# ROBOCON_25_SCHEMATIC_json.net
KiCad netlist of a schematic drawn in EasyEDA
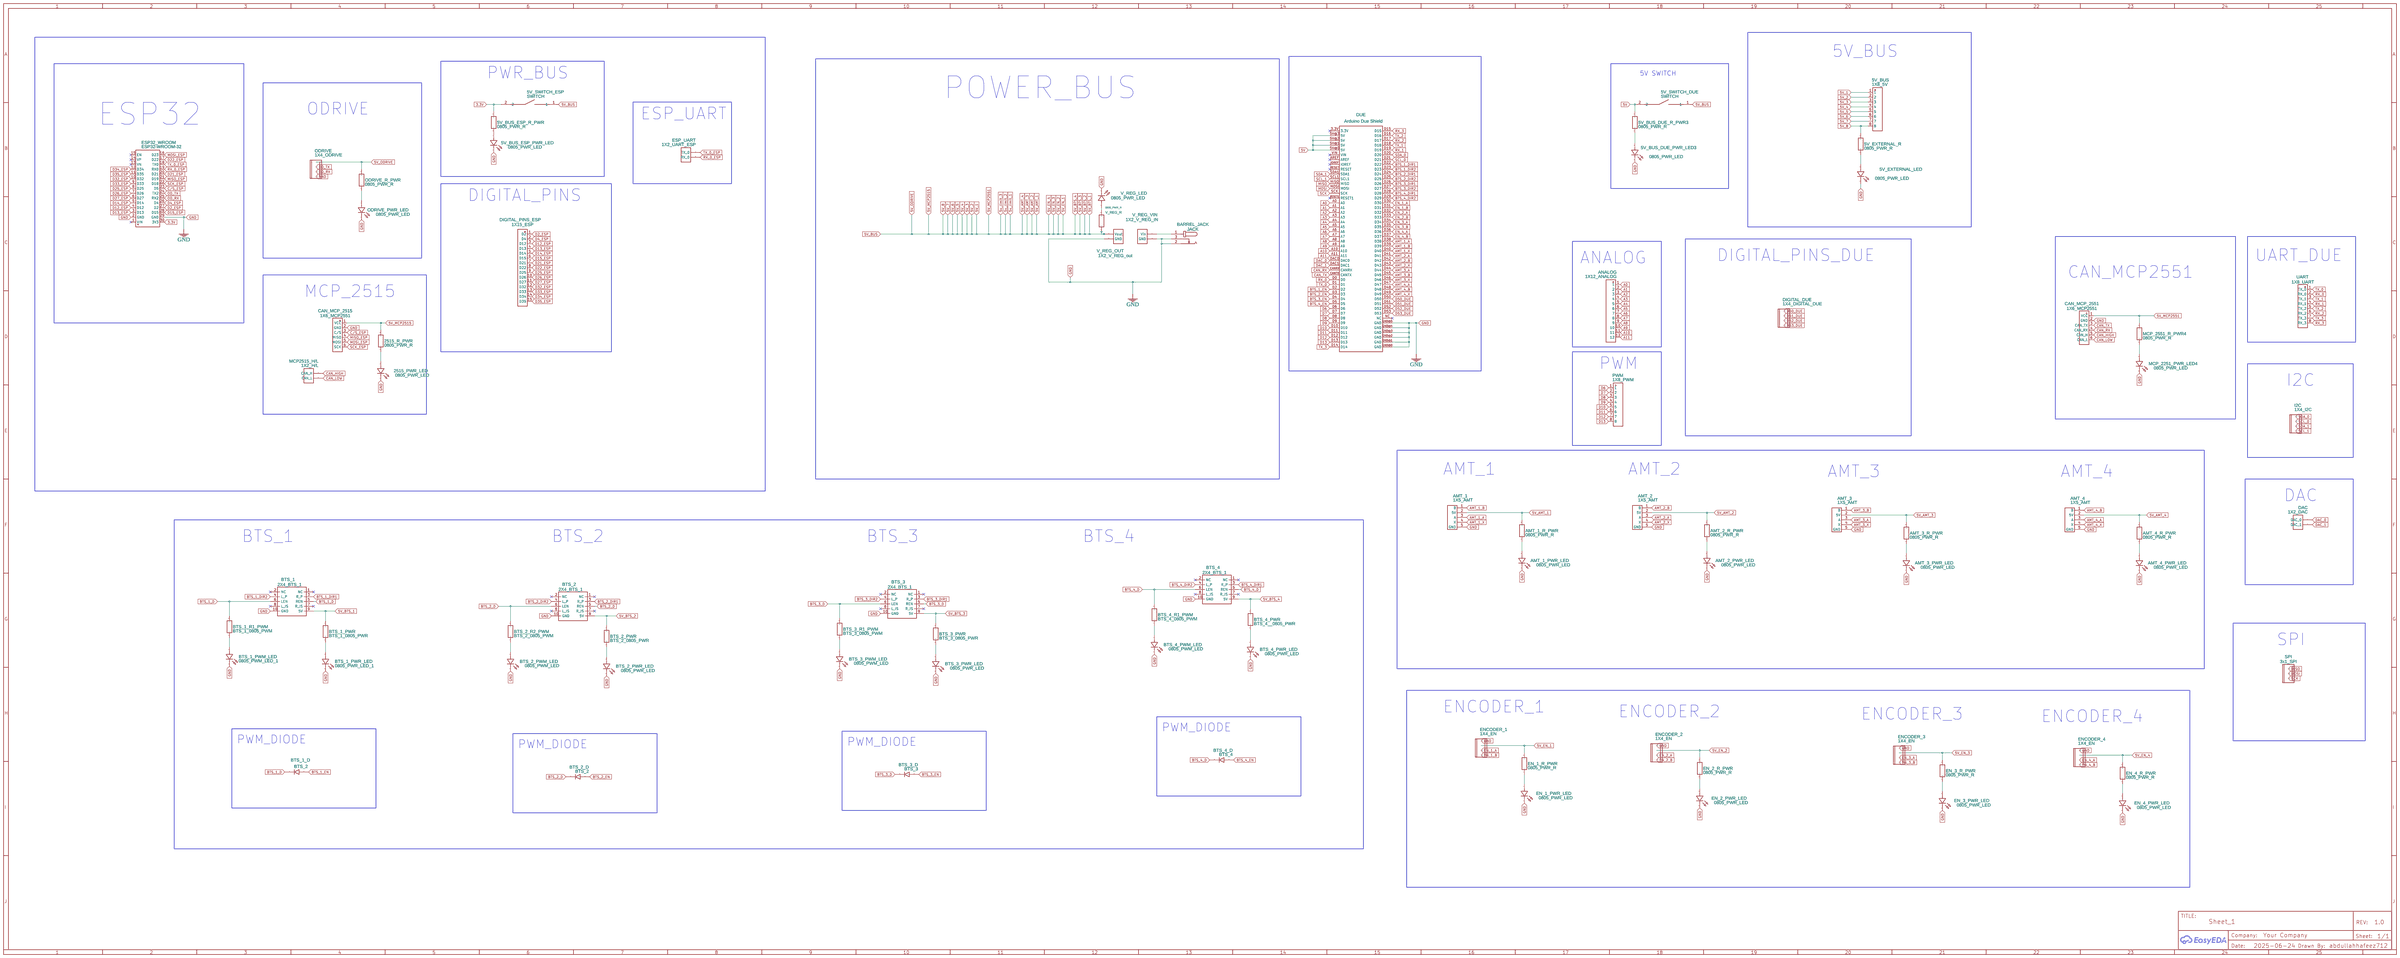
[diagram p0: schematic sheet]

(export (version "E")
  (design (tool "Eeschema 10.0.6"))
  (components
    (comp (ref "5V_BUS")
      (value "1X8_5V")
      (fields
        (field (name "Manufacturer Part") "HC-PZ200-8.7L-1x8PZ")
        (field (name "Manufacturer") "HC(虹成电子)")
      )
      (libsource (lib "") (part "HC-PZ200-8.7L-1X8PZ_2"))
    )
    (comp (ref "5V_BUS_DUE_PWR_LED3")
      (value "0805_PWR_LED")
      (fields (field (name "Manufacturer Part") "YLED0805YG") (field (name "Manufacturer") "YONGYUTAI(永裕泰)"))
      (libsource (lib "") (part "YLED0805YG_20"))
    )
    (comp (ref "5V_BUS_DUE_R_PWR3") (value "0805_PWR_R") (libsource (lib "") (part "RESISTOR-SMD-1206_6")))
    (comp (ref "5V_BUS_ESP_PWR_LED")
      (value "0805_PWR_LED")
      (fields (field (name "Manufacturer Part") "YLED0805YG") (field (name "Manufacturer") "YONGYUTAI(永裕泰)"))
      (libsource (lib "") (part "YLED0805YG_2"))
    )
    (comp (ref "5V_BUS_ESP_R_PWR") (value "0805_PWR_R") (libsource (lib "") (part "RESISTOR-SMD-1206")))
    (comp (ref "5V_EXTERNAL_LED")
      (value "0805_PWR_LED")
      (fields (field (name "Manufacturer Part") "YLED0805YG") (field (name "Manufacturer") "YONGYUTAI(永裕泰)"))
      (libsource (lib "") (part "YLED0805YG_4"))
    )
    (comp (ref "5V_EXTERNAL_R") (value "0805_PWR_R") (libsource (lib "") (part "RESISTOR-SMD-1206_2")))
    (comp (ref "5V_SWITCH_DUE") (value "SWITCH") (libsource (lib "") (part "Tactile switch SMD 2 Pin")))
    (comp (ref "5V_SWITCH_ESP") (value "SWITCH") (libsource (lib "") (part "Tactile switch SMD 2 Pin_1")))
    (comp (ref "2515_PWR_LED")
      (value "0805_PWR_LED")
      (fields (field (name "Manufacturer Part") "YLED0805YG") (field (name "Manufacturer") "YONGYUTAI(永裕泰)"))
      (libsource (lib "") (part "YLED0805YG_19"))
    )
    (comp (ref "2515_R_PWR") (value "0805_PWR_R") (libsource (lib "") (part "RESISTOR-SMD-1206_10")))
    (comp (ref "AMT_1")
      (value "1X5_AMT")
      (fields (field (name "Manufacturer Part") "XHB-5A") (field (name "Manufacturer") "BOOMELE(博穆精密)"))
      (libsource (lib "") (part "XHB-5A"))
    )
    (comp (ref "AMT_1_PWR_LED")
      (value "0805_PWR_LED")
      (fields (field (name "Manufacturer Part") "YLED0805YG") (field (name "Manufacturer") "YONGYUTAI(永裕泰)"))
      (libsource (lib "") (part "YLED0805YG_15"))
    )
    (comp (ref "AMT_1_R_PWR") (value "0805_PWR_R") (libsource (lib "") (part "RESISTOR-SMD-1206_12")))
    (comp (ref "AMT_2")
      (value "1X5_AMT")
      (fields (field (name "Manufacturer Part") "XHB-5A") (field (name "Manufacturer") "BOOMELE(博穆精密)"))
      (libsource (lib "") (part "XHB-5A"))
    )
    (comp (ref "AMT_2_PWR_LED")
      (value "0805_PWR_LED")
      (fields (field (name "Manufacturer Part") "YLED0805YG") (field (name "Manufacturer") "YONGYUTAI(永裕泰)"))
      (libsource (lib "") (part "YLED0805YG_12"))
    )
    (comp (ref "AMT_2_R_PWR") (value "0805_PWR_R") (libsource (lib "") (part "RESISTOR-SMD-1206_5")))
    (comp (ref "AMT_3")
      (value "1X5_AMT")
      (fields (field (name "Manufacturer Part") "XHB-5A") (field (name "Manufacturer") "BOOMELE(博穆精密)"))
      (libsource (lib "") (part "XHB-5A"))
    )
    (comp (ref "AMT_3_PWR_LED")
      (value "0805_PWR_LED")
      (fields (field (name "Manufacturer Part") "YLED0805YG") (field (name "Manufacturer") "YONGYUTAI(永裕泰)"))
      (libsource (lib "") (part "YLED0805YG_6"))
    )
    (comp (ref "AMT_3_R_PWR") (value "0805_PWR_R") (libsource (lib "") (part "RESISTOR-SMD-1206_17")))
    (comp (ref "AMT_4")
      (value "1X5_AMT")
      (fields (field (name "Manufacturer Part") "XHB-5A") (field (name "Manufacturer") "BOOMELE(博穆精密)"))
      (libsource (lib "") (part "XHB-5A"))
    )
    (comp (ref "AMT_4_PWR_LED")
      (value "0805_PWR_LED")
      (fields (field (name "Manufacturer Part") "YLED0805YG") (field (name "Manufacturer") "YONGYUTAI(永裕泰)"))
      (libsource (lib "") (part "YLED0805YG_1"))
    )
    (comp (ref "AMT_4_R_PWR") (value "0805_PWR_R") (libsource (lib "") (part "RESISTOR-SMD-1206_7")))
    (comp (ref "ANALOG")
      (value "1X12_ANALOG")
      (fields
        (field (name "Manufacturer Part") "KH-2FH-1X12P-H4.3")
        (field (name "Manufacturer") "kinghelm(金航标)")
      )
      (libsource (lib "") (part "KH-2FH-1X12P-H4.3"))
    )
    (comp (ref "BARREL_JACK")
      (value "JACK")
      (fields (field (name "Manufacturer Part") "PJ-002AH") (field (name "Manufacturer") "CUI"))
      (libsource (lib "") (part "PJ-002AH"))
    )
    (comp (ref "BTS_1") (value "2X4_BTS_1") (libsource (lib "") (part "IDC-10_(2X5)_2,54_BOX")))
    (comp (ref "BTS_1_D")
      (value "BTS_2")
      (fields (field (name "Manufacturer Part") "IRFD9120PbF"))
      (libsource (lib "") (part "IN4007_2"))
    )
    (comp (ref "BTS_1_PWM_LED")
      (value "0805_PWM_LED_1")
      (fields (field (name "Manufacturer Part") "YLED0805YG") (field (name "Manufacturer") "YONGYUTAI(永裕泰)"))
      (libsource (lib "") (part "YLED0805YG_18"))
    )
    (comp (ref "BTS_1_PWR") (value "BTS_1_0805_PWR") (libsource (lib "") (part "RESISTOR-SMD-1206_14")))
    (comp (ref "BTS_1_PWR_LED")
      (value "0805_PWR_LED_1")
      (fields (field (name "Manufacturer Part") "YLED0805YG") (field (name "Manufacturer") "YONGYUTAI(永裕泰)"))
      (libsource (lib "") (part "YLED0805YG_11"))
    )
    (comp (ref "BTS_1_R1_PWM") (value "BTS_1_0805_PWM") (libsource (lib "") (part "RESISTOR-SMD-1206_1")))
    (comp (ref "BTS_2") (value "2X4_BTS_1") (libsource (lib "") (part "IDC-10_(2X5)_2,54_BOX")))
    (comp (ref "BTS_2_D")
      (value "BTS_2")
      (fields (field (name "Manufacturer Part") "IRFD9120PbF"))
      (libsource (lib "") (part "IN4007_1"))
    )
    (comp (ref "BTS_2_PWM_LED")
      (value "0805_PWM_LED")
      (fields (field (name "Manufacturer Part") "YLED0805YG") (field (name "Manufacturer") "YONGYUTAI(永裕泰)"))
      (libsource (lib "") (part "YLED0805YG_5"))
    )
    (comp (ref "BTS_2_PWR") (value "BTS_2_0805_PWR") (libsource (lib "") (part "RESISTOR-SMD-1206_9")))
    (comp (ref "BTS_2_PWR_LED")
      (value "0805_PWR_LED")
      (fields (field (name "Manufacturer Part") "YLED0805YG") (field (name "Manufacturer") "YONGYUTAI(永裕泰)"))
      (libsource (lib "") (part "YLED0805YG_8"))
    )
    (comp (ref "BTS_2_R2_PWM") (value "BTS_2_0805_PWM") (libsource (lib "") (part "RESISTOR-SMD-1206_16")))
    (comp (ref "BTS_3") (value "2X4_BTS_1") (libsource (lib "") (part "IDC-10_(2X5)_2,54_BOX")))
    (comp (ref "BTS_3_D")
      (value "BTS_3")
      (fields (field (name "Manufacturer Part") "IRFD9120PbF"))
      (libsource (lib "") (part "IN4007"))
    )
    (comp (ref "BTS_3_PWM_LED")
      (value "0805_PWM_LED")
      (fields (field (name "Manufacturer Part") "YLED0805YG") (field (name "Manufacturer") "YONGYUTAI(永裕泰)"))
      (libsource (lib "") (part "YLED0805YG_10"))
    )
    (comp (ref "BTS_3_PWR") (value "BTS_3_0805_PWR") (libsource (lib "") (part "RESISTOR-SMD-1206_20")))
    (comp (ref "BTS_3_PWR_LED")
      (value "0805_PWR_LED")
      (fields (field (name "Manufacturer Part") "YLED0805YG") (field (name "Manufacturer") "YONGYUTAI(永裕泰)"))
      (libsource (lib "") (part "YLED0805YG_17"))
    )
    (comp (ref "BTS_3_R1_PWM") (value "BTS_3_0805_PWM") (libsource (lib "") (part "RESISTOR-SMD-1206_18")))
    (comp (ref "BTS_4") (value "2X4_BTS_1") (libsource (lib "") (part "IDC-10_(2X5)_2,54_BOX")))
    (comp (ref "BTS_4_D")
      (value "BTS_4")
      (fields (field (name "Manufacturer Part") "IRFD9120PbF"))
      (libsource (lib "") (part "IN4007_3"))
    )
    (comp (ref "BTS_4_PWM_LED")
      (value "0805_PWM_LED")
      (fields (field (name "Manufacturer Part") "YLED0805YG") (field (name "Manufacturer") "YONGYUTAI(永裕泰)"))
      (libsource (lib "") (part "YLED0805YG_9"))
    )
    (comp (ref "BTS_4_PWR") (value "BTS_4__0805_PWR") (libsource (lib "") (part "RESISTOR-SMD-1206_3")))
    (comp (ref "BTS_4_PWR_LED")
      (value "0805_PWR_LED")
      (fields (field (name "Manufacturer Part") "YLED0805YG") (field (name "Manufacturer") "YONGYUTAI(永裕泰)"))
      (libsource (lib "") (part "YLED0805YG_3"))
    )
    (comp (ref "BTS_4_R1_PWM") (value "BTS_4_0805_PWM") (libsource (lib "") (part "RESISTOR-SMD-1206_4")))
    (comp (ref "CAN_MCP_2515")
      (value "1X6_MCP2551")
      (fields (field (name "Manufacturer Part") "DS1021-1x6SF11-B") (field (name "Manufacturer") "CONNFLY"))
      (libsource (lib "") (part "DS1021-1X6SF11-B_1"))
    )
    (comp (ref "CAN_MCP_2551")
      (value "1X6_MCP2551")
      (fields (field (name "Manufacturer Part") "DS1021-1x6SF11-B") (field (name "Manufacturer") "CONNFLY"))
      (libsource (lib "") (part "DS1021-1X6SF11-B"))
    )
    (comp (ref "DAC")
      (value "1X2_DAC")
      (fields (field (name "Manufacturer Part") "RELIMATE CON 3 PIN"))
      (libsource (lib "") (part "2 pin RELIMATE copy_4"))
    )
    (comp (ref "DIGITAL_DUE")
      (value "1X4_DIGITAL_DUE")
      (libsource (lib "") (part "4PIN_RELIMATE_CONNECTOR_3"))
    )
    (comp (ref "DIGITAL_PINS_ESP")
      (value "1X15_ESP")
      (fields
        (field (name "Manufacturer Part") "HC-PM200-4.3H-1x15PZ")
        (field (name "Manufacturer") "HC(虹成电子)")
      )
      (libsource (lib "") (part "HC-PM200-4.3H-1X15PZ"))
    )
    (comp (ref "DUE")
      (value "Arduino Due Shield")
      (fields (field (name "Manufacturer Part") "ARDUINO DUE"))
      (libsource (lib "") (part "Arduino Due Shield"))
    )
    (comp (ref "ENCODER_1") (value "1X4_EN") (libsource (lib "") (part "4PIN_RELIMATE_CONNECTOR")))
    (comp (ref "ENCODER_2") (value "1X4_EN") (libsource (lib "") (part "4PIN_RELIMATE_CONNECTOR")))
    (comp (ref "ENCODER_3") (value "1X4_EN") (libsource (lib "") (part "4PIN_RELIMATE_CONNECTOR")))
    (comp (ref "ENCODER_4") (value "1X4_EN") (libsource (lib "") (part "4PIN_RELIMATE_CONNECTOR")))
    (comp (ref "EN_1_PWR_LED")
      (value "0805_PWR_LED")
      (fields (field (name "Manufacturer Part") "YLED0805YG") (field (name "Manufacturer") "YONGYUTAI(永裕泰)"))
      (libsource (lib "") (part "YLED0805YG_7"))
    )
    (comp (ref "EN_1_R_PWR") (value "0805_PWR_R") (libsource (lib "") (part "RESISTOR-SMD-1206_15")))
    (comp (ref "EN_2_PWR_LED")
      (value "0805_PWR_LED")
      (fields (field (name "Manufacturer Part") "YLED0805YG") (field (name "Manufacturer") "YONGYUTAI(永裕泰)"))
      (libsource (lib "") (part "YLED0805YG_14"))
    )
    (comp (ref "EN_2_R_PWR") (value "0805_PWR_R") (libsource (lib "") (part "RESISTOR-SMD-1206_19")))
    (comp (ref "EN_3_PWR_LED")
      (value "0805_PWR_LED")
      (fields (field (name "Manufacturer Part") "YLED0805YG") (field (name "Manufacturer") "YONGYUTAI(永裕泰)"))
      (libsource (lib "") (part "YLED0805YG_21"))
    )
    (comp (ref "EN_3_R_PWR") (value "0805_PWR_R") (libsource (lib "") (part "RESISTOR-SMD-1206_13")))
    (comp (ref "EN_4_PWR_LED")
      (value "0805_PWR_LED")
      (fields (field (name "Manufacturer Part") "YLED0805YG") (field (name "Manufacturer") "YONGYUTAI(永裕泰)"))
      (libsource (lib "") (part "YLED0805YG"))
    )
    (comp (ref "EN_4_R_PWR") (value "0805_PWR_R") (libsource (lib "") (part "RESISTOR-SMD-1206_22")))
    (comp (ref "ESP32_WROOM") (value "ESP32-WROOM-32") (libsource (lib "") (part "ESP32-WROOM-32-30Pin")))
    (comp (ref "ESP_UART")
      (value "1X2_UART_ESP")
      (fields (field (name "Manufacturer Part") "RELIMATE CON 3 PIN"))
      (libsource (lib "") (part "2 pin RELIMATE copy_3"))
    )
    (comp (ref "I2C") (value "1X4_I2C") (libsource (lib "") (part "4PIN_RELIMATE_CONNECTOR_1")))
    (comp (ref "MCP2515_H/L")
      (value "1X2_H/L")
      (fields (field (name "Manufacturer Part") "RELIMATE CON 3 PIN"))
      (libsource (lib "") (part "2 pin RELIMATE copy_1"))
    )
    (comp (ref "MCP_2251_PWR_LED4")
      (value "0805_PWR_LED")
      (fields (field (name "Manufacturer Part") "YLED0805YG") (field (name "Manufacturer") "YONGYUTAI(永裕泰)"))
      (libsource (lib "") (part "YLED0805YG_16"))
    )
    (comp (ref "MCP_2551_R_PWR4") (value "0805_PWR_R") (libsource (lib "") (part "RESISTOR-SMD-1206_8")))
    (comp (ref "ODRIVE") (value "1X4_ODRIVE") (libsource (lib "") (part "4PIN_RELIMATE_CONNECTOR_2")))
    (comp (ref "ODRIVE_PWR_LED")
      (value "0805_PWR_LED")
      (fields (field (name "Manufacturer Part") "YLED0805YG") (field (name "Manufacturer") "YONGYUTAI(永裕泰)"))
      (libsource (lib "") (part "YLED0805YG_22"))
    )
    (comp (ref "ODRIVE_R_PWR") (value "0805_PWR_R") (libsource (lib "") (part "RESISTOR-SMD-1206_11")))
    (comp (ref "PWM")
      (value "1X8_PWM")
      (fields
        (field (name "Manufacturer Part") "HC-PZ200-8.7L-1x8PZ")
        (field (name "Manufacturer") "HC(虹成电子)")
      )
      (libsource (lib "") (part "HC-PZ200-8.7L-1X8PZ"))
    )
    (comp (ref "SPI") (value "3x1_SPI") (libsource (lib "") (part "3PIN_RELIMATE_CONNECTOR")))
    (comp (ref "UART")
      (value "1X8_UART")
      (fields
        (field (name "Manufacturer Part") "HC-PZ200-8.7L-1x8PZ")
        (field (name "Manufacturer") "HC(虹成电子)")
      )
      (libsource (lib "") (part "HC-PZ200-8.7L-1X8PZ_1"))
    )
    (comp (ref "V_REG_LED")
      (value "0805_PWR_LED")
      (fields (field (name "Manufacturer Part") "YLED0805YG") (field (name "Manufacturer") "YONGYUTAI(永裕泰)"))
      (libsource (lib "") (part "YLED0805YG_13"))
    )
    (comp (ref "V_REG_OUT")
      (value "1X2_V_REG_out")
      (fields (field (name "Manufacturer Part") "RELIMATE CON 3 PIN"))
      (libsource (lib "") (part "2 pin RELIMATE copy"))
    )
    (comp (ref "V_REG_R") (value "0805_PWR_R") (libsource (lib "") (part "RESISTOR-SMD-1206_21")))
    (comp (ref "V_REG_VIN")
      (value "1X2_V_REG_IN")
      (fields (field (name "Manufacturer Part") "RELIMATE CON 3 PIN"))
      (libsource (lib "") (part "2 pin RELIMATE copy_2"))
    )
  )
  (nets
    (net (code "1") (name "3.3V") (class "Default")
      (node (ref "5V_BUS_ESP_R_PWR") (pin "2") (pinfunction "2_2") (pintype "unspecified"))
      (node (ref "5V_SWITCH_ESP") (pin "2") (pinfunction "2_2") (pintype "unspecified"))
      (node (ref "ESP32_WROOM") (pin "30") (pinfunction "3V3_30") (pintype "unspecified"))
    )
    (net (code "2") (name "5V") (class "Default")
      (node (ref "5V_BUS_DUE_R_PWR3") (pin "2") (pinfunction "2_2") (pintype "unspecified"))
      (node (ref "5V_SWITCH_DUE") (pin "2") (pinfunction "2_2") (pintype "unspecified"))
      (node (ref "DUE") (pin "5V@0") (pinfunction "5V_5V@0") (pintype "unspecified"))
      (node (ref "DUE") (pin "5V@1") (pinfunction "5V_5V@1") (pintype "unspecified"))
      (node (ref "DUE") (pin "5V@2") (pinfunction "5V_5V@2") (pintype "unspecified"))
      (node (ref "DUE") (pin "5V@3") (pinfunction "5V_5V@3") (pintype "unspecified"))
    )
    (net (code "3") (name "5V_1") (class "Default")
      (node (ref "2515_R_PWR") (pin "2") (pinfunction "2_2") (pintype "unspecified"))
      (node (ref "5V_BUS") (pin "1") (pinfunction "1_1") (pintype "unspecified"))
      (node (ref "5V_BUS") (pin "2") (pinfunction "2_2") (pintype "unspecified"))
      (node (ref "5V_BUS") (pin "3") (pinfunction "3_3") (pintype "unspecified"))
      (node (ref "5V_BUS") (pin "4") (pinfunction "4_4") (pintype "unspecified"))
      (node (ref "5V_BUS") (pin "5") (pinfunction "5_5") (pintype "unspecified"))
      (node (ref "5V_BUS") (pin "6") (pinfunction "6_6") (pintype "unspecified"))
      (node (ref "5V_BUS") (pin "7") (pinfunction "7_7") (pintype "unspecified"))
      (node (ref "5V_BUS") (pin "8") (pinfunction "8_8") (pintype "unspecified"))
      (node (ref "5V_EXTERNAL_R") (pin "2") (pinfunction "2_2") (pintype "unspecified"))
      (node (ref "5V_SWITCH_DUE") (pin "1") (pinfunction "1_1") (pintype "unspecified"))
      (node (ref "5V_SWITCH_ESP") (pin "1") (pinfunction "1_1") (pintype "unspecified"))
      (node (ref "AMT_1") (pin "2") (pinfunction "5V_2") (pintype "unspecified"))
      (node (ref "AMT_1_R_PWR") (pin "2") (pinfunction "2_2") (pintype "unspecified"))
      (node (ref "AMT_2") (pin "2") (pinfunction "5V_2") (pintype "unspecified"))
      (node (ref "AMT_2_R_PWR") (pin "2") (pinfunction "2_2") (pintype "unspecified"))
      (node (ref "AMT_3") (pin "2") (pinfunction "5V_2") (pintype "unspecified"))
      (node (ref "AMT_3_R_PWR") (pin "2") (pinfunction "2_2") (pintype "unspecified"))
      (node (ref "AMT_4") (pin "2") (pinfunction "5V_2") (pintype "unspecified"))
      (node (ref "AMT_4_R_PWR") (pin "2") (pinfunction "2_2") (pintype "unspecified"))
      (node (ref "BTS_1") (pin "9") (pinfunction "5V_9") (pintype "unspecified"))
      (node (ref "BTS_1_PWR") (pin "2") (pinfunction "2_2") (pintype "unspecified"))
      (node (ref "BTS_2") (pin "9") (pinfunction "5V_9") (pintype "unspecified"))
      (node (ref "BTS_2_PWR") (pin "2") (pinfunction "2_2") (pintype "unspecified"))
      (node (ref "BTS_3") (pin "9") (pinfunction "5V_9") (pintype "unspecified"))
      (node (ref "BTS_3_PWR") (pin "2") (pinfunction "2_2") (pintype "unspecified"))
      (node (ref "BTS_4") (pin "9") (pinfunction "5V_9") (pintype "unspecified"))
      (node (ref "BTS_4_PWR") (pin "2") (pinfunction "2_2") (pintype "unspecified"))
      (node (ref "CAN_MCP_2515") (pin "1") (pinfunction "VCC_1") (pintype "unspecified"))
      (node (ref "CAN_MCP_2551") (pin "1") (pinfunction "VCC_1") (pintype "unspecified"))
      (node (ref "ENCODER_1") (pin "3") (pinfunction "A_3") (pintype "bidirectional"))
      (node (ref "ENCODER_2") (pin "3") (pinfunction "A_3") (pintype "bidirectional"))
      (node (ref "ENCODER_3") (pin "3") (pinfunction "A_3") (pintype "bidirectional"))
      (node (ref "ENCODER_4") (pin "3") (pinfunction "A_3") (pintype "bidirectional"))
      (node (ref "EN_1_R_PWR") (pin "2") (pinfunction "2_2") (pintype "unspecified"))
      (node (ref "EN_2_R_PWR") (pin "2") (pinfunction "2_2") (pintype "unspecified"))
      (node (ref "EN_3_R_PWR") (pin "2") (pinfunction "2_2") (pintype "unspecified"))
      (node (ref "EN_4_R_PWR") (pin "2") (pinfunction "2_2") (pintype "unspecified"))
      (node (ref "MCP_2551_R_PWR4") (pin "2") (pinfunction "2_2") (pintype "unspecified"))
      (node (ref "ODRIVE") (pin "4") (pinfunction "GND_4") (pintype "bidirectional"))
      (node (ref "ODRIVE_R_PWR") (pin "2") (pinfunction "2_2") (pintype "unspecified"))
      (node (ref "V_REG_OUT") (pin "1") (pinfunction "Vout_1") (pintype "unspecified"))
      (node (ref "V_REG_R") (pin "1") (pinfunction "1_1") (pintype "unspecified"))
    )
    (net (code "4") (name "A0") (class "Default")
      (node (ref "ANALOG") (pin "1") (pinfunction "1_1") (pintype "unspecified"))
      (node (ref "DUE") (pin "A0") (pinfunction "A0_A0") (pintype "unspecified"))
    )
    (net (code "5") (name "A1") (class "Default")
      (node (ref "ANALOG") (pin "2") (pinfunction "2_2") (pintype "unspecified"))
      (node (ref "DUE") (pin "A1") (pinfunction "A1_A1") (pintype "unspecified"))
    )
    (net (code "6") (name "A2") (class "Default")
      (node (ref "ANALOG") (pin "3") (pinfunction "3_3") (pintype "unspecified"))
      (node (ref "DUE") (pin "A2") (pinfunction "A2_A2") (pintype "unspecified"))
    )
    (net (code "7") (name "A3") (class "Default")
      (node (ref "ANALOG") (pin "4") (pinfunction "4_4") (pintype "unspecified"))
      (node (ref "DUE") (pin "A3") (pinfunction "A3_A3") (pintype "unspecified"))
    )
    (net (code "8") (name "A4") (class "Default")
      (node (ref "ANALOG") (pin "5") (pinfunction "5_5") (pintype "unspecified"))
      (node (ref "DUE") (pin "A4") (pinfunction "A4_A4") (pintype "unspecified"))
    )
    (net (code "9") (name "A5") (class "Default")
      (node (ref "ANALOG") (pin "6") (pinfunction "6_6") (pintype "unspecified"))
      (node (ref "DUE") (pin "A5") (pinfunction "A5_A5") (pintype "unspecified"))
    )
    (net (code "10") (name "A6") (class "Default")
      (node (ref "ANALOG") (pin "7") (pinfunction "7_7") (pintype "unspecified"))
      (node (ref "DUE") (pin "A6") (pinfunction "A6_A6") (pintype "unspecified"))
    )
    (net (code "11") (name "A7") (class "Default")
      (node (ref "ANALOG") (pin "8") (pinfunction "8_8") (pintype "unspecified"))
      (node (ref "DUE") (pin "A7") (pinfunction "A7_A7") (pintype "unspecified"))
    )
    (net (code "12") (name "A8") (class "Default")
      (node (ref "ANALOG") (pin "9") (pinfunction "9_9") (pintype "unspecified"))
      (node (ref "DUE") (pin "A8") (pinfunction "A8_A8") (pintype "unspecified"))
    )
    (net (code "13") (name "A9") (class "Default")
      (node (ref "ANALOG") (pin "10") (pinfunction "10_10") (pintype "unspecified"))
      (node (ref "DUE") (pin "A9") (pinfunction "A9_A9") (pintype "unspecified"))
    )
    (net (code "14") (name "A10") (class "Default")
      (node (ref "ANALOG") (pin "11") (pinfunction "11_11") (pintype "unspecified"))
      (node (ref "DUE") (pin "A10") (pinfunction "A10_A10") (pintype "unspecified"))
    )
    (net (code "15") (name "A11") (class "Default")
      (node (ref "ANALOG") (pin "12") (pinfunction "12_12") (pintype "unspecified"))
      (node (ref "DUE") (pin "A11") (pinfunction "A11_A11") (pintype "unspecified"))
    )
    (net (code "16") (name "AMT_1_A") (class "Default")
      (node (ref "AMT_1") (pin "3") (pinfunction "A_3") (pintype "unspecified"))
      (node (ref "DUE") (pin "D38") (pinfunction "D38_D38") (pintype "unspecified"))
    )
    (net (code "17") (name "AMT_1_B") (class "Default")
      (node (ref "AMT_1") (pin "1") (pinfunction "B_1") (pintype "unspecified"))
      (node (ref "DUE") (pin "D39") (pinfunction "D39_D39") (pintype "unspecified"))
    )
    (net (code "18") (name "AMT_1_X") (class "Default")
      (node (ref "AMT_1") (pin "4") (pinfunction "X_4") (pintype "unspecified"))
      (node (ref "DUE") (pin "D40") (pinfunction "D40_D40") (pintype "unspecified"))
    )
    (net (code "19") (name "AMT_2_A") (class "Default")
      (node (ref "AMT_2") (pin "3") (pinfunction "A_3") (pintype "unspecified"))
      (node (ref "DUE") (pin "D41") (pinfunction "D41_D41") (pintype "unspecified"))
    )
    (net (code "20") (name "AMT_2_B") (class "Default")
      (node (ref "AMT_2") (pin "1") (pinfunction "B_1") (pintype "unspecified"))
      (node (ref "DUE") (pin "D42") (pinfunction "D42_D42") (pintype "unspecified"))
    )
    (net (code "21") (name "AMT_2_X") (class "Default")
      (node (ref "AMT_2") (pin "4") (pinfunction "X_4") (pintype "unspecified"))
      (node (ref "DUE") (pin "D43") (pinfunction "D43_D43") (pintype "unspecified"))
    )
    (net (code "22") (name "AMT_3_A") (class "Default")
      (node (ref "AMT_3") (pin "3") (pinfunction "A_3") (pintype "unspecified"))
      (node (ref "DUE") (pin "D44") (pinfunction "D44_D44") (pintype "unspecified"))
    )
    (net (code "23") (name "AMT_3_B") (class "Default")
      (node (ref "AMT_3") (pin "1") (pinfunction "B_1") (pintype "unspecified"))
      (node (ref "DUE") (pin "D45") (pinfunction "D45_D45") (pintype "unspecified"))
    )
    (net (code "24") (name "AMT_3_X") (class "Default")
      (node (ref "AMT_3") (pin "4") (pinfunction "X_4") (pintype "unspecified"))
      (node (ref "DUE") (pin "D46") (pinfunction "D46_D46") (pintype "unspecified"))
    )
    (net (code "25") (name "AMT_4_A") (class "Default")
      (node (ref "AMT_4") (pin "3") (pinfunction "A_3") (pintype "unspecified"))
      (node (ref "DUE") (pin "D47") (pinfunction "D47_D47") (pintype "unspecified"))
    )
    (net (code "26") (name "AMT_4_B") (class "Default")
      (node (ref "AMT_4") (pin "1") (pinfunction "B_1") (pintype "unspecified"))
      (node (ref "DUE") (pin "D48") (pinfunction "D48_D48") (pintype "unspecified"))
    )
    (net (code "27") (name "AMT_4_X") (class "Default")
      (node (ref "AMT_4") (pin "4") (pinfunction "X_4") (pintype "unspecified"))
      (node (ref "DUE") (pin "D49") (pinfunction "D49_D49") (pintype "unspecified"))
    )
    (net (code "28") (name "BTS_1_D") (class "Default")
      (node (ref "BTS_1") (pin "5") (pinfunction "REN_5") (pintype "unspecified"))
      (node (ref "BTS_1") (pin "6") (pinfunction "LEN_6") (pintype "unspecified"))
      (node (ref "BTS_1_D") (pin "1") (pinfunction "1_1") (pintype "unspecified"))
      (node (ref "BTS_1_R1_PWM") (pin "2") (pinfunction "2_2") (pintype "unspecified"))
    )
    (net (code "29") (name "BTS_1_DIR1") (class "Default")
      (node (ref "BTS_1") (pin "3") (pinfunction "R_P_3") (pintype "unspecified"))
      (node (ref "DUE") (pin "D22") (pinfunction "D22_D22") (pintype "unspecified"))
    )
    (net (code "30") (name "BTS_1_DIR2") (class "Default")
      (node (ref "BTS_1") (pin "4") (pinfunction "L_P_4") (pintype "unspecified"))
      (node (ref "DUE") (pin "D23") (pinfunction "D23_D23") (pintype "unspecified"))
    )
    (net (code "31") (name "BTS_1_EN") (class "Default")
      (node (ref "BTS_1_D") (pin "2") (pinfunction "2_2") (pintype "unspecified"))
      (node (ref "DUE") (pin "D2") (pinfunction "D2_D2") (pintype "unspecified"))
    )
    (net (code "32") (name "BTS_2_D") (class "Default")
      (node (ref "BTS_2") (pin "5") (pinfunction "REN_5") (pintype "unspecified"))
      (node (ref "BTS_2") (pin "6") (pinfunction "LEN_6") (pintype "unspecified"))
      (node (ref "BTS_2_D") (pin "1") (pinfunction "1_1") (pintype "unspecified"))
      (node (ref "BTS_2_R2_PWM") (pin "2") (pinfunction "2_2") (pintype "unspecified"))
    )
    (net (code "33") (name "BTS_2_DIR1") (class "Default")
      (node (ref "BTS_2") (pin "3") (pinfunction "R_P_3") (pintype "unspecified"))
      (node (ref "DUE") (pin "D24") (pinfunction "D24_D24") (pintype "unspecified"))
    )
    (net (code "34") (name "BTS_2_DIR2") (class "Default")
      (node (ref "BTS_2") (pin "4") (pinfunction "L_P_4") (pintype "unspecified"))
      (node (ref "DUE") (pin "D25") (pinfunction "D25_D25") (pintype "unspecified"))
    )
    (net (code "35") (name "BTS_2_EN") (class "Default")
      (node (ref "BTS_2_D") (pin "2") (pinfunction "2_2") (pintype "unspecified"))
      (node (ref "DUE") (pin "D3") (pinfunction "D3_D3") (pintype "unspecified"))
    )
    (net (code "36") (name "BTS_3_D") (class "Default")
      (node (ref "BTS_3") (pin "5") (pinfunction "REN_5") (pintype "unspecified"))
      (node (ref "BTS_3") (pin "6") (pinfunction "LEN_6") (pintype "unspecified"))
      (node (ref "BTS_3_D") (pin "1") (pinfunction "1_1") (pintype "unspecified"))
      (node (ref "BTS_3_R1_PWM") (pin "2") (pinfunction "2_2") (pintype "unspecified"))
    )
    (net (code "37") (name "BTS_3_DIR1") (class "Default")
      (node (ref "BTS_3") (pin "3") (pinfunction "R_P_3") (pintype "unspecified"))
      (node (ref "DUE") (pin "D26") (pinfunction "D26_D26") (pintype "unspecified"))
    )
    (net (code "38") (name "BTS_3_DIR2") (class "Default")
      (node (ref "BTS_3") (pin "4") (pinfunction "L_P_4") (pintype "unspecified"))
      (node (ref "DUE") (pin "D27") (pinfunction "D27_D27") (pintype "unspecified"))
    )
    (net (code "39") (name "BTS_3_EN") (class "Default")
      (node (ref "BTS_3_D") (pin "2") (pinfunction "2_2") (pintype "unspecified"))
      (node (ref "DUE") (pin "D4") (pinfunction "D4_D4") (pintype "unspecified"))
    )
    (net (code "40") (name "BTS_4_D") (class "Default")
      (node (ref "BTS_4") (pin "5") (pinfunction "REN_5") (pintype "unspecified"))
      (node (ref "BTS_4") (pin "6") (pinfunction "LEN_6") (pintype "unspecified"))
      (node (ref "BTS_4_D") (pin "1") (pinfunction "1_1") (pintype "unspecified"))
      (node (ref "BTS_4_R1_PWM") (pin "2") (pinfunction "2_2") (pintype "unspecified"))
    )
    (net (code "41") (name "BTS_4_DIR1") (class "Default")
      (node (ref "BTS_4") (pin "3") (pinfunction "R_P_3") (pintype "unspecified"))
      (node (ref "DUE") (pin "D28") (pinfunction "D28_D28") (pintype "unspecified"))
    )
    (net (code "42") (name "BTS_4_DIR2") (class "Default")
      (node (ref "BTS_4") (pin "4") (pinfunction "L_P_4") (pintype "unspecified"))
      (node (ref "DUE") (pin "D29") (pinfunction "D29_D29") (pintype "unspecified"))
    )
    (net (code "43") (name "BTS_4_EN") (class "Default")
      (node (ref "BTS_4_D") (pin "2") (pinfunction "2_2") (pintype "unspecified"))
      (node (ref "DUE") (pin "D5") (pinfunction "D5_D5") (pintype "unspecified"))
    )
    (net (code "44") (name "CAN_HIGH") (class "Default")
      (node (ref "CAN_MCP_2551") (pin "5") (pinfunction "CAN_H_5") (pintype "unspecified"))
      (node (ref "MCP2515_H/L") (pin "1") (pinfunction "CAN_H_1") (pintype "unspecified"))
    )
    (net (code "45") (name "CAN_LOW") (class "Default")
      (node (ref "CAN_MCP_2551") (pin "6") (pinfunction "CAN_L_6") (pintype "unspecified"))
      (node (ref "MCP2515_H/L") (pin "2") (pinfunction "CAN_L_2") (pintype "unspecified"))
    )
    (net (code "46") (name "CAN_RX") (class "Default")
      (node (ref "CAN_MCP_2551") (pin "4") (pinfunction "CAN_RX_4") (pintype "unspecified"))
      (node (ref "DUE") (pin "CANRX") (pinfunction "CANRX_CANRX") (pintype "unspecified"))
    )
    (net (code "47") (name "CAN_TX") (class "Default")
      (node (ref "CAN_MCP_2551") (pin "3") (pinfunction "CAN_TX_3") (pintype "unspecified"))
      (node (ref "DUE") (pin "CANTX") (pinfunction "CANTX_CANTX") (pintype "unspecified"))
    )
    (net (code "48") (name "C{slash}S_ESP") (class "Default")
      (node (ref "CAN_MCP_2515") (pin "3") (pinfunction "C/S_3") (pintype "unspecified"))
      (node (ref "ESP32_WROOM") (pin "23") (pinfunction "D5_23") (pintype "unspecified"))
    )
    (net (code "49") (name "D2_ESP") (class "Default")
      (node (ref "DIGITAL_PINS_ESP") (pin "1") (pinfunction "D2_1") (pintype "unspecified"))
      (node (ref "ESP32_WROOM") (pin "27") (pinfunction "D2_27") (pintype "unspecified"))
    )
    (net (code "50") (name "D4_ESP") (class "Default")
      (node (ref "DIGITAL_PINS_ESP") (pin "2") (pinfunction "D4_2") (pintype "unspecified"))
      (node (ref "ESP32_WROOM") (pin "26") (pinfunction "D4_26") (pintype "unspecified"))
    )
    (net (code "51") (name "D6") (class "Default")
      (node (ref "DUE") (pin "D6") (pinfunction "D6_D6") (pintype "unspecified"))
      (node (ref "PWM") (pin "1") (pinfunction "1_1") (pintype "unspecified"))
    )
    (net (code "52") (name "D7") (class "Default")
      (node (ref "DUE") (pin "D7") (pinfunction "D7_D7") (pintype "unspecified"))
      (node (ref "PWM") (pin "2") (pinfunction "2_2") (pintype "unspecified"))
    )
    (net (code "53") (name "D8") (class "Default")
      (node (ref "DUE") (pin "D8") (pinfunction "D8_D8") (pintype "unspecified"))
      (node (ref "PWM") (pin "3") (pinfunction "3_3") (pintype "unspecified"))
    )
    (net (code "54") (name "D9") (class "Default")
      (node (ref "DUE") (pin "D9") (pinfunction "D9_D9") (pintype "unspecified"))
      (node (ref "PWM") (pin "4") (pinfunction "4_4") (pintype "unspecified"))
    )
    (net (code "55") (name "D10") (class "Default")
      (node (ref "DUE") (pin "D10") (pinfunction "D10_D10") (pintype "unspecified"))
      (node (ref "PWM") (pin "5") (pinfunction "5_5") (pintype "unspecified"))
    )
    (net (code "56") (name "D11") (class "Default")
      (node (ref "DUE") (pin "D11") (pinfunction "D11_D11") (pintype "unspecified"))
      (node (ref "PWM") (pin "6") (pinfunction "6_6") (pintype "unspecified"))
    )
    (net (code "57") (name "D12") (class "Default")
      (node (ref "DUE") (pin "D12") (pinfunction "D12_D12") (pintype "unspecified"))
      (node (ref "PWM") (pin "7") (pinfunction "7_7") (pintype "unspecified"))
    )
    (net (code "58") (name "D12_ESP") (class "Default")
      (node (ref "DIGITAL_PINS_ESP") (pin "3") (pinfunction "D12_3") (pintype "unspecified"))
      (node (ref "ESP32_WROOM") (pin "4") (pinfunction "D12_4") (pintype "unspecified"))
    )
    (net (code "59") (name "D13") (class "Default")
      (node (ref "DUE") (pin "D13") (pinfunction "D13_D13") (pintype "unspecified"))
      (node (ref "PWM") (pin "8") (pinfunction "8_8") (pintype "unspecified"))
    )
    (net (code "60") (name "D13_ESP") (class "Default")
      (node (ref "DIGITAL_PINS_ESP") (pin "4") (pinfunction "D13_4") (pintype "unspecified"))
      (node (ref "ESP32_WROOM") (pin "3") (pinfunction "D13_3") (pintype "unspecified"))
    )
    (net (code "61") (name "D14_ESP") (class "Default")
      (node (ref "DIGITAL_PINS_ESP") (pin "5") (pinfunction "D14_5") (pintype "unspecified"))
      (node (ref "ESP32_WROOM") (pin "5") (pinfunction "D14_5") (pintype "unspecified"))
    )
    (net (code "62") (name "D15_ESP") (class "Default")
      (node (ref "DIGITAL_PINS_ESP") (pin "6") (pinfunction "D15_6") (pintype "unspecified"))
      (node (ref "ESP32_WROOM") (pin "28") (pinfunction "D15_28") (pintype "unspecified"))
    )
    (net (code "63") (name "D21_ESP") (class "Default")
      (node (ref "DIGITAL_PINS_ESP") (pin "7") (pinfunction "D21_7") (pintype "unspecified"))
      (node (ref "ESP32_WROOM") (pin "20") (pinfunction "D21_20") (pintype "unspecified"))
    )
    (net (code "64") (name "D22_ESP") (class "Default")
      (node (ref "DIGITAL_PINS_ESP") (pin "8") (pinfunction "D22_8") (pintype "unspecified"))
      (node (ref "ESP32_WROOM") (pin "17") (pinfunction "D22_17") (pintype "unspecified"))
    )
    (net (code "65") (name "D25_ESP") (class "Default")
      (node (ref "DIGITAL_PINS_ESP") (pin "9") (pinfunction "D25_9") (pintype "unspecified"))
      (node (ref "ESP32_WROOM") (pin "8") (pinfunction "D25_8") (pintype "unspecified"))
    )
    (net (code "66") (name "D26_ESP") (class "Default")
      (node (ref "DIGITAL_PINS_ESP") (pin "10") (pinfunction "D26_10") (pintype "unspecified"))
      (node (ref "ESP32_WROOM") (pin "7") (pinfunction "D26_7") (pintype "unspecified"))
    )
    (net (code "67") (name "D27_ESP") (class "Default")
      (node (ref "DIGITAL_PINS_ESP") (pin "11") (pinfunction "D27_11") (pintype "unspecified"))
      (node (ref "ESP32_WROOM") (pin "6") (pinfunction "D27_6") (pintype "unspecified"))
    )
    (net (code "68") (name "D32_ESP") (class "Default")
      (node (ref "DIGITAL_PINS_ESP") (pin "12") (pinfunction "D32_12") (pintype "unspecified"))
      (node (ref "ESP32_WROOM") (pin "10") (pinfunction "D32_10") (pintype "unspecified"))
    )
    (net (code "69") (name "D33_ESP") (class "Default")
      (node (ref "DIGITAL_PINS_ESP") (pin "13") (pinfunction "D33_13") (pintype "unspecified"))
      (node (ref "ESP32_WROOM") (pin "9") (pinfunction "D33_9") (pintype "unspecified"))
    )
    (net (code "70") (name "D34_ESP") (class "Default")
      (node (ref "DIGITAL_PINS_ESP") (pin "14") (pinfunction "D34_14") (pintype "unspecified"))
      (node (ref "ESP32_WROOM") (pin "12") (pinfunction "D34_12") (pintype "unspecified"))
    )
    (net (code "71") (name "D35_ESP") (class "Default")
      (node (ref "DIGITAL_PINS_ESP") (pin "15") (pinfunction "D35_15") (pintype "unspecified"))
      (node (ref "ESP32_WROOM") (pin "11") (pinfunction "D35_11") (pintype "unspecified"))
    )
    (net (code "72") (name "D50_DUE") (class "Default")
      (node (ref "DIGITAL_DUE") (pin "4") (pinfunction "D40_4") (pintype "bidirectional"))
      (node (ref "DUE") (pin "D50") (pinfunction "D50_D50") (pintype "unspecified"))
    )
    (net (code "73") (name "D51_DUE") (class "Default")
      (node (ref "DIGITAL_DUE") (pin "3") (pinfunction "D51_3") (pintype "bidirectional"))
      (node (ref "DUE") (pin "D51") (pinfunction "D51_D51") (pintype "unspecified"))
    )
    (net (code "74") (name "D52_DUE") (class "Default")
      (node (ref "DIGITAL_DUE") (pin "2") (pinfunction "D52_2") (pintype "bidirectional"))
      (node (ref "DUE") (pin "D52") (pinfunction "D52_D52") (pintype "unspecified"))
    )
    (net (code "75") (name "D53_DUE") (class "Default")
      (node (ref "DIGITAL_DUE") (pin "1") (pinfunction "D53_1") (pintype "bidirectional"))
      (node (ref "DUE") (pin "D53") (pinfunction "D53_D53") (pintype "unspecified"))
    )
    (net (code "76") (name "DAC_0") (class "Default")
      (node (ref "DAC") (pin "1") (pinfunction "DAC_0_1") (pintype "unspecified"))
      (node (ref "DUE") (pin "DAC0") (pinfunction "DAC0_DAC0") (pintype "unspecified"))
    )
    (net (code "77") (name "DAC_1") (class "Default")
      (node (ref "DAC") (pin "2") (pinfunction "DAC_1_2") (pintype "unspecified"))
      (node (ref "DUE") (pin "DAC1") (pinfunction "DAC1_DAC1") (pintype "unspecified"))
    )
    (net (code "78") (name "EN_1_A") (class "Default")
      (node (ref "DUE") (pin "D30") (pinfunction "D30_D30") (pintype "unspecified"))
      (node (ref "ENCODER_1") (pin "2") (pinfunction "B_2") (pintype "bidirectional"))
    )
    (net (code "79") (name "EN_1_B") (class "Default")
      (node (ref "DUE") (pin "D31") (pinfunction "D31_D31") (pintype "unspecified"))
      (node (ref "ENCODER_1") (pin "1") (pinfunction "VCC_1") (pintype "bidirectional"))
    )
    (net (code "80") (name "EN_2_A") (class "Default")
      (node (ref "DUE") (pin "D32") (pinfunction "D32_D32") (pintype "unspecified"))
      (node (ref "ENCODER_2") (pin "2") (pinfunction "B_2") (pintype "bidirectional"))
    )
    (net (code "81") (name "EN_2_B") (class "Default")
      (node (ref "DUE") (pin "D33") (pinfunction "D33_D33") (pintype "unspecified"))
      (node (ref "ENCODER_2") (pin "1") (pinfunction "VCC_1") (pintype "bidirectional"))
    )
    (net (code "82") (name "EN_3_A") (class "Default")
      (node (ref "DUE") (pin "D34") (pinfunction "D34_D34") (pintype "unspecified"))
      (node (ref "ENCODER_3") (pin "2") (pinfunction "B_2") (pintype "bidirectional"))
    )
    (net (code "83") (name "EN_3_B") (class "Default")
      (node (ref "DUE") (pin "D35") (pinfunction "D35_D35") (pintype "unspecified"))
      (node (ref "ENCODER_3") (pin "1") (pinfunction "VCC_1") (pintype "bidirectional"))
    )
    (net (code "84") (name "EN_4_A") (class "Default")
      (node (ref "DUE") (pin "D36") (pinfunction "D36_D36") (pintype "unspecified"))
      (node (ref "ENCODER_4") (pin "2") (pinfunction "B_2") (pintype "bidirectional"))
    )
    (net (code "85") (name "EN_4_B") (class "Default")
      (node (ref "DUE") (pin "D37") (pinfunction "D37_D37") (pintype "unspecified"))
      (node (ref "ENCODER_4") (pin "1") (pinfunction "VCC_1") (pintype "bidirectional"))
    )
    (net (code "86") (name "GND") (class "Default")
      (node (ref "2515_PWR_LED") (pin "2") (pinfunction "2_2") (pintype "unspecified"))
      (node (ref "5V_BUS_DUE_PWR_LED3") (pin "2") (pinfunction "2_2") (pintype "unspecified"))
      (node (ref "5V_BUS_ESP_PWR_LED") (pin "2") (pinfunction "2_2") (pintype "unspecified"))
      (node (ref "5V_EXTERNAL_LED") (pin "2") (pinfunction "2_2") (pintype "unspecified"))
      (node (ref "AMT_1") (pin "5") (pinfunction "GND_5") (pintype "unspecified"))
      (node (ref "AMT_1_PWR_LED") (pin "2") (pinfunction "2_2") (pintype "unspecified"))
      (node (ref "AMT_2") (pin "5") (pinfunction "GND_5") (pintype "unspecified"))
      (node (ref "AMT_2_PWR_LED") (pin "2") (pinfunction "2_2") (pintype "unspecified"))
      (node (ref "AMT_3") (pin "5") (pinfunction "GND_5") (pintype "unspecified"))
      (node (ref "AMT_3_PWR_LED") (pin "2") (pinfunction "2_2") (pintype "unspecified"))
      (node (ref "AMT_4") (pin "5") (pinfunction "GND_5") (pintype "unspecified"))
      (node (ref "AMT_4_PWR_LED") (pin "2") (pinfunction "2_2") (pintype "unspecified"))
      (node (ref "BARREL_JACK") (pin "2") (pinfunction "2_2") (pintype "unspecified"))
      (node (ref "BARREL_JACK") (pin "3") (pinfunction "3_3") (pintype "unspecified"))
      (node (ref "BTS_1") (pin "10") (pinfunction "GND_10") (pintype "unspecified"))
      (node (ref "BTS_1_PWM_LED") (pin "2") (pinfunction "2_2") (pintype "unspecified"))
      (node (ref "BTS_1_PWR_LED") (pin "2") (pinfunction "2_2") (pintype "unspecified"))
      (node (ref "BTS_2") (pin "10") (pinfunction "GND_10") (pintype "unspecified"))
      (node (ref "BTS_2_PWM_LED") (pin "2") (pinfunction "2_2") (pintype "unspecified"))
      (node (ref "BTS_2_PWR_LED") (pin "2") (pinfunction "2_2") (pintype "unspecified"))
      (node (ref "BTS_3") (pin "10") (pinfunction "GND_10") (pintype "unspecified"))
      (node (ref "BTS_3_PWM_LED") (pin "2") (pinfunction "2_2") (pintype "unspecified"))
      (node (ref "BTS_3_PWR_LED") (pin "2") (pinfunction "2_2") (pintype "unspecified"))
      (node (ref "BTS_4") (pin "10") (pinfunction "GND_10") (pintype "unspecified"))
      (node (ref "BTS_4_PWM_LED") (pin "2") (pinfunction "2_2") (pintype "unspecified"))
      (node (ref "BTS_4_PWR_LED") (pin "2") (pinfunction "2_2") (pintype "unspecified"))
      (node (ref "CAN_MCP_2515") (pin "2") (pinfunction "GND_2") (pintype "unspecified"))
      (node (ref "CAN_MCP_2551") (pin "2") (pinfunction "GND_2") (pintype "unspecified"))
      (node (ref "DUE") (pin "GND@0") (pinfunction "GND_GND@0") (pintype "unspecified"))
      (node (ref "DUE") (pin "GND@1") (pinfunction "GND_GND@1") (pintype "unspecified"))
      (node (ref "DUE") (pin "GND@2") (pinfunction "GND_GND@2") (pintype "unspecified"))
      (node (ref "DUE") (pin "GND@3") (pinfunction "GND_GND@3") (pintype "unspecified"))
      (node (ref "DUE") (pin "GND@4") (pinfunction "GND_GND@4") (pintype "unspecified"))
      (node (ref "DUE") (pin "GND@5") (pinfunction "GND_GND@5") (pintype "unspecified"))
      (node (ref "ENCODER_1") (pin "4") (pinfunction "GND_4") (pintype "bidirectional"))
      (node (ref "ENCODER_2") (pin "4") (pinfunction "GND_4") (pintype "bidirectional"))
      (node (ref "ENCODER_3") (pin "4") (pinfunction "GND_4") (pintype "bidirectional"))
      (node (ref "ENCODER_4") (pin "4") (pinfunction "GND_4") (pintype "bidirectional"))
      (node (ref "EN_1_PWR_LED") (pin "2") (pinfunction "2_2") (pintype "unspecified"))
      (node (ref "EN_2_PWR_LED") (pin "2") (pinfunction "2_2") (pintype "unspecified"))
      (node (ref "EN_3_PWR_LED") (pin "2") (pinfunction "2_2") (pintype "unspecified"))
      (node (ref "EN_4_PWR_LED") (pin "2") (pinfunction "2_2") (pintype "unspecified"))
      (node (ref "ESP32_WROOM") (pin "2") (pinfunction "GND_2") (pintype "unspecified"))
      (node (ref "ESP32_WROOM") (pin "29") (pinfunction "GND_29") (pintype "unspecified"))
      (node (ref "MCP_2251_PWR_LED4") (pin "2") (pinfunction "2_2") (pintype "unspecified"))
      (node (ref "ODRIVE") (pin "1") (pinfunction "VCC_1") (pintype "bidirectional"))
      (node (ref "ODRIVE_PWR_LED") (pin "2") (pinfunction "2_2") (pintype "unspecified"))
      (node (ref "V_REG_LED") (pin "2") (pinfunction "2_2") (pintype "unspecified"))
      (node (ref "V_REG_OUT") (pin "2") (pinfunction "GND_2") (pintype "unspecified"))
      (node (ref "V_REG_VIN") (pin "2") (pinfunction "GND_2") (pintype "unspecified"))
    )
    (net (code "87") (name "MISO") (class "Default")
      (node (ref "DUE") (pin "MISO") (pinfunction "MISO_MISO") (pintype "unspecified"))
      (node (ref "SPI") (pin "3") (pinfunction "MISO_3") (pintype "bidirectional"))
    )
    (net (code "88") (name "MISO_ESP") (class "Default")
      (node (ref "CAN_MCP_2515") (pin "4") (pinfunction "MISO_4") (pintype "unspecified"))
      (node (ref "ESP32_WROOM") (pin "21") (pinfunction "D19_21") (pintype "unspecified"))
    )
    (net (code "89") (name "MOSI") (class "Default")
      (node (ref "DUE") (pin "MOSI") (pinfunction "MOSI_MOSI") (pintype "unspecified"))
      (node (ref "SPI") (pin "2") (pinfunction "MOSI_2") (pintype "bidirectional"))
    )
    (net (code "90") (name "MOSI_ESP") (class "Default")
      (node (ref "CAN_MCP_2515") (pin "5") (pinfunction "MOSI_5") (pintype "unspecified"))
      (node (ref "ESP32_WROOM") (pin "16") (pinfunction "D23_16") (pintype "unspecified"))
    )
    (net (code "91") (name "Net-(5V_BUS_DUE_PWR_LED3-Pad1)") (class "Default")
      (node (ref "5V_BUS_DUE_PWR_LED3") (pin "1") (pinfunction "1_1") (pintype "unspecified"))
      (node (ref "5V_BUS_DUE_R_PWR3") (pin "1") (pinfunction "1_1") (pintype "unspecified"))
    )
    (net (code "92") (name "Net-(5V_BUS_ESP_PWR_LED-Pad1)") (class "Default")
      (node (ref "5V_BUS_ESP_PWR_LED") (pin "1") (pinfunction "1_1") (pintype "unspecified"))
      (node (ref "5V_BUS_ESP_R_PWR") (pin "1") (pinfunction "1_1") (pintype "unspecified"))
    )
    (net (code "93") (name "Net-(5V_EXTERNAL_LED-Pad1)") (class "Default")
      (node (ref "5V_EXTERNAL_LED") (pin "1") (pinfunction "1_1") (pintype "unspecified"))
      (node (ref "5V_EXTERNAL_R") (pin "1") (pinfunction "1_1") (pintype "unspecified"))
    )
    (net (code "94") (name "Net-(2515_PWR_LED-Pad1)") (class "Default")
      (node (ref "2515_PWR_LED") (pin "1") (pinfunction "1_1") (pintype "unspecified"))
      (node (ref "2515_R_PWR") (pin "1") (pinfunction "1_1") (pintype "unspecified"))
    )
    (net (code "95") (name "Net-(AMT_1_PWR_LED-Pad1)") (class "Default")
      (node (ref "AMT_1_PWR_LED") (pin "1") (pinfunction "1_1") (pintype "unspecified"))
      (node (ref "AMT_1_R_PWR") (pin "1") (pinfunction "1_1") (pintype "unspecified"))
    )
    (net (code "96") (name "Net-(AMT_2_PWR_LED-Pad1)") (class "Default")
      (node (ref "AMT_2_PWR_LED") (pin "1") (pinfunction "1_1") (pintype "unspecified"))
      (node (ref "AMT_2_R_PWR") (pin "1") (pinfunction "1_1") (pintype "unspecified"))
    )
    (net (code "97") (name "Net-(AMT_3_PWR_LED-Pad1)") (class "Default")
      (node (ref "AMT_3_PWR_LED") (pin "1") (pinfunction "1_1") (pintype "unspecified"))
      (node (ref "AMT_3_R_PWR") (pin "1") (pinfunction "1_1") (pintype "unspecified"))
    )
    (net (code "98") (name "Net-(AMT_4_PWR_LED-Pad1)") (class "Default")
      (node (ref "AMT_4_PWR_LED") (pin "1") (pinfunction "1_1") (pintype "unspecified"))
      (node (ref "AMT_4_R_PWR") (pin "1") (pinfunction "1_1") (pintype "unspecified"))
    )
    (net (code "99") (name "Net-(BTS_1_PWM_LED-Pad1)") (class "Default")
      (node (ref "BTS_1_PWM_LED") (pin "1") (pinfunction "1_1") (pintype "unspecified"))
      (node (ref "BTS_1_R1_PWM") (pin "1") (pinfunction "1_1") (pintype "unspecified"))
    )
    (net (code "100") (name "Net-(BTS_1_PWR-Pad1)") (class "Default")
      (node (ref "BTS_1_PWR") (pin "1") (pinfunction "1_1") (pintype "unspecified"))
      (node (ref "BTS_1_PWR_LED") (pin "1") (pinfunction "1_1") (pintype "unspecified"))
    )
    (net (code "101") (name "Net-(BTS_2_PWM_LED-Pad1)") (class "Default")
      (node (ref "BTS_2_PWM_LED") (pin "1") (pinfunction "1_1") (pintype "unspecified"))
      (node (ref "BTS_2_R2_PWM") (pin "1") (pinfunction "1_1") (pintype "unspecified"))
    )
    (net (code "102") (name "Net-(BTS_2_PWR-Pad1)") (class "Default")
      (node (ref "BTS_2_PWR") (pin "1") (pinfunction "1_1") (pintype "unspecified"))
      (node (ref "BTS_2_PWR_LED") (pin "1") (pinfunction "1_1") (pintype "unspecified"))
    )
    (net (code "103") (name "Net-(BTS_3_PWM_LED-Pad1)") (class "Default")
      (node (ref "BTS_3_PWM_LED") (pin "1") (pinfunction "1_1") (pintype "unspecified"))
      (node (ref "BTS_3_R1_PWM") (pin "1") (pinfunction "1_1") (pintype "unspecified"))
    )
    (net (code "104") (name "Net-(BTS_3_PWR-Pad1)") (class "Default")
      (node (ref "BTS_3_PWR") (pin "1") (pinfunction "1_1") (pintype "unspecified"))
      (node (ref "BTS_3_PWR_LED") (pin "1") (pinfunction "1_1") (pintype "unspecified"))
    )
    (net (code "105") (name "Net-(BTS_4_PWM_LED-Pad1)") (class "Default")
      (node (ref "BTS_4_PWM_LED") (pin "1") (pinfunction "1_1") (pintype "unspecified"))
      (node (ref "BTS_4_R1_PWM") (pin "1") (pinfunction "1_1") (pintype "unspecified"))
    )
    (net (code "106") (name "Net-(BTS_4_PWR-Pad1)") (class "Default")
      (node (ref "BTS_4_PWR") (pin "1") (pinfunction "1_1") (pintype "unspecified"))
      (node (ref "BTS_4_PWR_LED") (pin "1") (pinfunction "1_1") (pintype "unspecified"))
    )
    (net (code "107") (name "Net-(EN_1_PWR_LED-Pad1)") (class "Default")
      (node (ref "EN_1_PWR_LED") (pin "1") (pinfunction "1_1") (pintype "unspecified"))
      (node (ref "EN_1_R_PWR") (pin "1") (pinfunction "1_1") (pintype "unspecified"))
    )
    (net (code "108") (name "Net-(EN_2_PWR_LED-Pad1)") (class "Default")
      (node (ref "EN_2_PWR_LED") (pin "1") (pinfunction "1_1") (pintype "unspecified"))
      (node (ref "EN_2_R_PWR") (pin "1") (pinfunction "1_1") (pintype "unspecified"))
    )
    (net (code "109") (name "Net-(EN_3_PWR_LED-Pad1)") (class "Default")
      (node (ref "EN_3_PWR_LED") (pin "1") (pinfunction "1_1") (pintype "unspecified"))
      (node (ref "EN_3_R_PWR") (pin "1") (pinfunction "1_1") (pintype "unspecified"))
    )
    (net (code "110") (name "Net-(EN_4_PWR_LED-Pad1)") (class "Default")
      (node (ref "EN_4_PWR_LED") (pin "1") (pinfunction "1_1") (pintype "unspecified"))
      (node (ref "EN_4_R_PWR") (pin "1") (pinfunction "1_1") (pintype "unspecified"))
    )
    (net (code "111") (name "Net-(MCP_2251_PWR_LED4-Pad1)") (class "Default")
      (node (ref "MCP_2251_PWR_LED4") (pin "1") (pinfunction "1_1") (pintype "unspecified"))
      (node (ref "MCP_2551_R_PWR4") (pin "1") (pinfunction "1_1") (pintype "unspecified"))
    )
    (net (code "112") (name "Net-(ODRIVE_PWR_LED-Pad1)") (class "Default")
      (node (ref "ODRIVE_PWR_LED") (pin "1") (pinfunction "1_1") (pintype "unspecified"))
      (node (ref "ODRIVE_R_PWR") (pin "1") (pinfunction "1_1") (pintype "unspecified"))
    )
    (net (code "113") (name "Net-(V_REG_LED-Pad1)") (class "Default")
      (node (ref "V_REG_LED") (pin "1") (pinfunction "1_1") (pintype "unspecified"))
      (node (ref "V_REG_R") (pin "2") (pinfunction "2_2") (pintype "unspecified"))
    )
    (net (code "114") (name "Net-(V_REG_VIN-Vin)") (class "Default")
      (node (ref "BARREL_JACK") (pin "1") (pinfunction "1_1") (pintype "unspecified"))
      (node (ref "V_REG_VIN") (pin "1") (pinfunction "Vin_1") (pintype "unspecified"))
    )
    (net (code "115") (name "OD_RX") (class "Default")
      (node (ref "ESP32_WROOM") (pin "25") (pinfunction "RX2_25") (pintype "unspecified"))
      (node (ref "ODRIVE") (pin "2") (pinfunction "B_2") (pintype "bidirectional"))
    )
    (net (code "116") (name "OD_TX") (class "Default")
      (node (ref "ESP32_WROOM") (pin "24") (pinfunction "TX2_24") (pintype "unspecified"))
      (node (ref "ODRIVE") (pin "3") (pinfunction "A_3") (pintype "bidirectional"))
    )
    (net (code "117") (name "RX_0") (class "Default")
      (node (ref "DUE") (pin "D0") (pinfunction "D0_D0") (pintype "unspecified"))
      (node (ref "UART") (pin "2") (pinfunction "RX_0_2") (pintype "unspecified"))
    )
    (net (code "118") (name "RX_0_ESP") (class "Default")
      (node (ref "ESP32_WROOM") (pin "19") (pinfunction "RX0_19") (pintype "unspecified"))
      (node (ref "ESP_UART") (pin "2") (pinfunction "RX_0_2") (pintype "unspecified"))
    )
    (net (code "119") (name "RX_1") (class "Default")
      (node (ref "DUE") (pin "D19") (pinfunction "D19_D19") (pintype "unspecified"))
      (node (ref "UART") (pin "4") (pinfunction "RX_1_4") (pintype "unspecified"))
    )
    (net (code "120") (name "RX_2") (class "Default")
      (node (ref "DUE") (pin "D17") (pinfunction "D17_D17") (pintype "unspecified"))
      (node (ref "UART") (pin "6") (pinfunction "RX_2_6") (pintype "unspecified"))
    )
    (net (code "121") (name "RX_3") (class "Default")
      (node (ref "DUE") (pin "D15") (pinfunction "D15_D15") (pintype "unspecified"))
      (node (ref "UART") (pin "8") (pinfunction "RX_3_8") (pintype "unspecified"))
    )
    (net (code "122") (name "SCK") (class "Default")
      (node (ref "DUE") (pin "SCK") (pinfunction "SCK_SCK") (pintype "unspecified"))
      (node (ref "SPI") (pin "1") (pinfunction "SCK_1") (pintype "bidirectional"))
    )
    (net (code "123") (name "SCK_ESP") (class "Default")
      (node (ref "CAN_MCP_2515") (pin "6") (pinfunction "SCK_6") (pintype "unspecified"))
      (node (ref "ESP32_WROOM") (pin "22") (pinfunction "D18_22") (pintype "unspecified"))
    )
    (net (code "124") (name "SCL_0") (class "Default")
      (node (ref "DUE") (pin "D21") (pinfunction "D21_D21") (pintype "unspecified"))
      (node (ref "I2C") (pin "3") (pinfunction "SCL_0_3") (pintype "bidirectional"))
    )
    (net (code "125") (name "SCL_1") (class "Default")
      (node (ref "DUE") (pin "SCL1") (pinfunction "SCL1_SCL1") (pintype "unspecified"))
      (node (ref "I2C") (pin "1") (pinfunction "SCL_1_1") (pintype "bidirectional"))
    )
    (net (code "126") (name "SDA_0") (class "Default")
      (node (ref "DUE") (pin "D20") (pinfunction "D20_D20") (pintype "unspecified"))
      (node (ref "I2C") (pin "4") (pinfunction "SDA_0_4") (pintype "bidirectional"))
    )
    (net (code "127") (name "SDA_1") (class "Default")
      (node (ref "DUE") (pin "SDA1") (pinfunction "SDA1_SDA1") (pintype "unspecified"))
      (node (ref "I2C") (pin "2") (pinfunction "SDA_1_2") (pintype "bidirectional"))
    )
    (net (code "128") (name "TX_0") (class "Default")
      (node (ref "DUE") (pin "D1") (pinfunction "D1_D1") (pintype "unspecified"))
      (node (ref "UART") (pin "1") (pinfunction "TX_0_1") (pintype "unspecified"))
    )
    (net (code "129") (name "TX_0_ESP") (class "Default")
      (node (ref "ESP32_WROOM") (pin "18") (pinfunction "TX0_18") (pintype "unspecified"))
      (node (ref "ESP_UART") (pin "1") (pinfunction "TX_0_1") (pintype "unspecified"))
    )
    (net (code "130") (name "TX_1") (class "Default")
      (node (ref "DUE") (pin "D18") (pinfunction "D18_D18") (pintype "unspecified"))
      (node (ref "UART") (pin "3") (pinfunction "TX_1_3") (pintype "unspecified"))
    )
    (net (code "131") (name "TX_2") (class "Default")
      (node (ref "DUE") (pin "D16") (pinfunction "D16_D16") (pintype "unspecified"))
      (node (ref "UART") (pin "5") (pinfunction "TX_2_5") (pintype "unspecified"))
    )
    (net (code "132") (name "TX_3") (class "Default")
      (node (ref "DUE") (pin "D14") (pinfunction "D14_D14") (pintype "unspecified"))
      (node (ref "UART") (pin "7") (pinfunction "TX_3_7") (pintype "unspecified"))
    )
    (net (code "133") (name "unconnected-(BTS_1-L_IS-Pad8)") (class "Default")
      (node (ref "BTS_1") (pin "8") (pinfunction "L_IS_8") (pintype "unspecified+no_connect"))
    )
    (net (code "134") (name "unconnected-(BTS_1-NC-Pad1)") (class "Default")
      (node (ref "BTS_1") (pin "1") (pinfunction "NC_1") (pintype "unspecified+no_connect"))
    )
    (net (code "135") (name "unconnected-(BTS_1-NC-Pad2)") (class "Default")
      (node (ref "BTS_1") (pin "2") (pinfunction "NC_2") (pintype "unspecified+no_connect"))
    )
    (net (code "136") (name "unconnected-(BTS_1-R_IS-Pad7)") (class "Default")
      (node (ref "BTS_1") (pin "7") (pinfunction "R_IS_7") (pintype "unspecified+no_connect"))
    )
    (net (code "137") (name "unconnected-(BTS_2-L_IS-Pad8)") (class "Default")
      (node (ref "BTS_2") (pin "8") (pinfunction "L_IS_8") (pintype "unspecified+no_connect"))
    )
    (net (code "138") (name "unconnected-(BTS_2-NC-Pad1)") (class "Default")
      (node (ref "BTS_2") (pin "1") (pinfunction "NC_1") (pintype "unspecified+no_connect"))
    )
    (net (code "139") (name "unconnected-(BTS_2-NC-Pad2)") (class "Default")
      (node (ref "BTS_2") (pin "2") (pinfunction "NC_2") (pintype "unspecified+no_connect"))
    )
    (net (code "140") (name "unconnected-(BTS_2-R_IS-Pad7)") (class "Default")
      (node (ref "BTS_2") (pin "7") (pinfunction "R_IS_7") (pintype "unspecified+no_connect"))
    )
    (net (code "141") (name "unconnected-(BTS_3-L_IS-Pad8)") (class "Default")
      (node (ref "BTS_3") (pin "8") (pinfunction "L_IS_8") (pintype "unspecified+no_connect"))
    )
    (net (code "142") (name "unconnected-(BTS_3-NC-Pad1)") (class "Default")
      (node (ref "BTS_3") (pin "1") (pinfunction "NC_1") (pintype "unspecified+no_connect"))
    )
    (net (code "143") (name "unconnected-(BTS_3-NC-Pad2)") (class "Default")
      (node (ref "BTS_3") (pin "2") (pinfunction "NC_2") (pintype "unspecified+no_connect"))
    )
    (net (code "144") (name "unconnected-(BTS_3-R_IS-Pad7)") (class "Default")
      (node (ref "BTS_3") (pin "7") (pinfunction "R_IS_7") (pintype "unspecified+no_connect"))
    )
    (net (code "145") (name "unconnected-(BTS_4-L_IS-Pad8)") (class "Default")
      (node (ref "BTS_4") (pin "8") (pinfunction "L_IS_8") (pintype "unspecified+no_connect"))
    )
    (net (code "146") (name "unconnected-(BTS_4-NC-Pad1)") (class "Default")
      (node (ref "BTS_4") (pin "1") (pinfunction "NC_1") (pintype "unspecified+no_connect"))
    )
    (net (code "147") (name "unconnected-(BTS_4-NC-Pad2)") (class "Default")
      (node (ref "BTS_4") (pin "2") (pinfunction "NC_2") (pintype "unspecified+no_connect"))
    )
    (net (code "148") (name "unconnected-(BTS_4-R_IS-Pad7)") (class "Default")
      (node (ref "BTS_4") (pin "7") (pinfunction "R_IS_7") (pintype "unspecified+no_connect"))
    )
    (net (code "149") (name "unconnected-(DUE-Pad3.3V)") (class "Default")
      (node (ref "DUE") (pin "3.3V") (pinfunction "3.3V_3.3V") (pintype "unspecified+no_connect"))
    )
    (net (code "150") (name "unconnected-(DUE-PadAREF)") (class "Default")
      (node (ref "DUE") (pin "AREF") (pinfunction "AREF_AREF") (pintype "unspecified+no_connect"))
    )
    (net (code "151") (name "unconnected-(DUE-PadIOREF)") (class "Default")
      (node (ref "DUE") (pin "IOREF") (pinfunction "IOREF_IOREF") (pintype "unspecified+no_connect"))
    )
    (net (code "152") (name "unconnected-(DUE-PadNC)") (class "Default")
      (node (ref "DUE") (pin "NC") (pinfunction "NC_NC") (pintype "unspecified+no_connect"))
    )
    (net (code "153") (name "unconnected-(DUE-PadRESET)") (class "Default")
      (node (ref "DUE") (pin "RESET") (pinfunction "RESET_RESET") (pintype "unspecified+no_connect"))
    )
    (net (code "154") (name "unconnected-(DUE-PadRESET1)") (class "Default")
      (node (ref "DUE") (pin "RESET1") (pinfunction "RESET1_RESET1") (pintype "unspecified+no_connect"))
    )
    (net (code "155") (name "unconnected-(DUE-PadVIN)") (class "Default")
      (node (ref "DUE") (pin "VIN") (pinfunction "VIN_VIN") (pintype "unspecified+no_connect"))
    )
    (net (code "156") (name "unconnected-(ESP32_WROOM-EN-Pad15)") (class "Default")
      (node (ref "ESP32_WROOM") (pin "15") (pinfunction "EN_15") (pintype "unspecified+no_connect"))
    )
    (net (code "157") (name "unconnected-(ESP32_WROOM-VIN-Pad1)") (class "Default")
      (node (ref "ESP32_WROOM") (pin "1") (pinfunction "VIN_1") (pintype "unspecified+no_connect"))
    )
    (net (code "158") (name "unconnected-(ESP32_WROOM-VN-Pad13)") (class "Default")
      (node (ref "ESP32_WROOM") (pin "13") (pinfunction "VN_13") (pintype "unspecified+no_connect"))
    )
    (net (code "159") (name "unconnected-(ESP32_WROOM-VP-Pad14)") (class "Default")
      (node (ref "ESP32_WROOM") (pin "14") (pinfunction "VP_14") (pintype "unspecified+no_connect"))
    )
  )
)
